# BNO005.net
KiCad netlist of a schematic drawn in Altium Designer
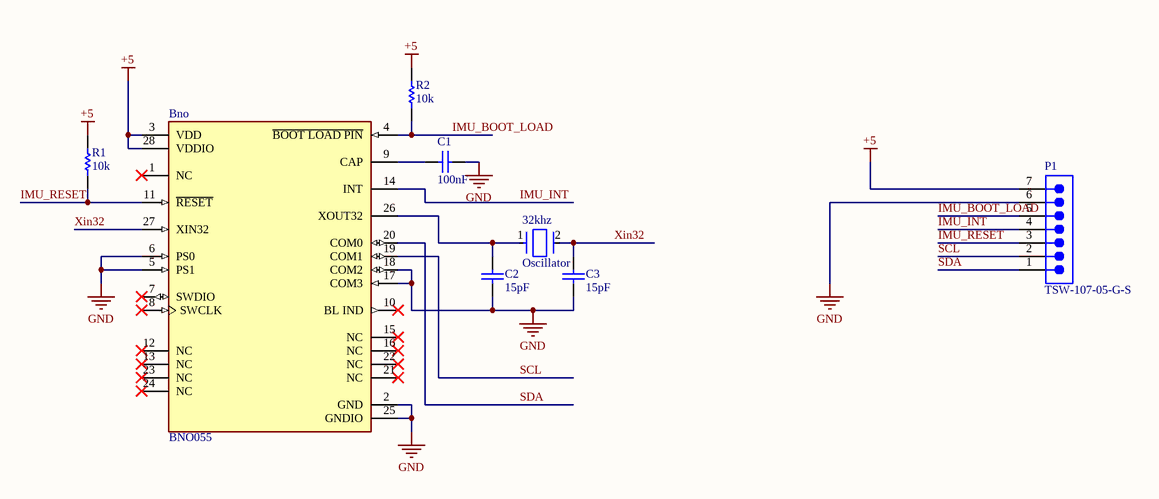
[diagram p0: BNO005.SchDoc]

(export (version "E")
  (design (tool "Eeschema 10.0.6"))
  (components
    (comp (ref "32khz")
      (value "Oscillator")
      (footprint "FP-NX2012SA-MFG")
      (description "CRYSTAL 32.7680KHZ 12.5PF SMD")
      (libsource (lib "Altium Content Vault") (part "c23a69dc6c9e2f18f2079038eb95dd1"))
    )
    (comp (ref "Bno")
      (value "BNO055")
      (footprint "FP-BNO055-MFG")
      (description "IMU ACCEL/GYRO/MAG I2C 28LGA")
      (libsource (lib "Altium Content Vault") (part "ba837af00a0b6167256f888b31462b1"))
    )
    (comp (ref "C1")
      (value "100nF")
      (footprint "CAPC1608X90X35ML10T15")
      (description "Chip Capacitor, 0.1 uF, +/- 10%, 50 V, -55 to 125 degC, 0603 (1608 Metric), RoHS, Tape and Reel")
      (fields (field (name "TOLERANCE") "10%") (field (name "VOLTAGE") "50V"))
      (libsource (lib "Altium Content Vault") (part "CAP-NP-2"))
    )
    (comp (ref "C2")
      (value "15pF")
      (footprint "CAPC1608X90X35ML10T15")
      (fields (field (name "PART NUMBER") "GRM1885C1H150JA01D") (field (name "MANUFACTURER") "Murata"))
      (libsource (lib "Altium Content Vault") (part "CAP"))
    )
    (comp (ref "C3")
      (value "15pF")
      (footprint "CAPC1608X90X35ML10T15")
      (fields (field (name "PART NUMBER") "GRM1885C1H150JA01D") (field (name "MANUFACTURER") "Murata"))
      (libsource (lib "Altium Content Vault") (part "CAP"))
    )
    (comp (ref "P1")
      (value "TSW-107-05-G-S")
      (footprint "SMTC-TSW-107-05-X-S")
      (description "0.025\" SQ Post Header, Through-hole, Vertical, -55 to 125 degC, 2.54 mm Pitch, 7-Pin, Male, RoHS")
      (fields (field (name "MANUFACTURER") "Samtec"))
      (libsource (lib "Altium Content Vault") (part "SMTC-TSW-107-05-X-S"))
    )
    (comp (ref "R1")
      (value "10k")
      (footprint "RESC1609X55X30LL15T15")
      (description "Chip Resistor, 10 KOhm, +/- 1%, 0.1 W, -55 to 155 degC, 0603 (1608 Metric), RoHS, Tape and Reel")
      (fields (field (name "TOLERANCE") "1%") (field (name "MANUFACTURER") "Panasonic"))
      (libsource (lib "Altium Content Vault") (part "RES-2"))
    )
    (comp (ref "R2")
      (value "10k")
      (footprint "RESC1609X55X30LL15T15")
      (description "Chip Resistor, 10 KOhm, +/- 1%, 0.1 W, -55 to 155 degC, 0603 (1608 Metric), RoHS, Tape and Reel")
      (fields (field (name "TOLERANCE") "1%") (field (name "MANUFACTURER") "Panasonic"))
      (libsource (lib "Altium Content Vault") (part "RES-2"))
    )
  )
  (nets
    (net (code "1") (name "+5") (class "Default")
      (node (ref "Bno") (pin "28") (pinfunction "VDDIO_28") (pintype "power_in"))
      (node (ref "Bno") (pin "3") (pinfunction "VDD_3") (pintype "power_in"))
      (node (ref "P1") (pin "7") (pinfunction "7_7") (pintype "passive"))
      (node (ref "R1") (pin "2") (pinfunction "2_2") (pintype "passive"))
      (node (ref "R2") (pin "2") (pinfunction "2_2") (pintype "passive"))
    )
    (net (code "2") (name "/IMU_BOOT_LOAD") (class "Default")
      (node (ref "Bno") (pin "4") (pinfunction "~{BOOT_LOAD_PIN}_4") (pintype "input"))
      (node (ref "P1") (pin "5") (pinfunction "5_5") (pintype "passive"))
      (node (ref "R2") (pin "1") (pinfunction "1_1") (pintype "passive"))
    )
    (net (code "3") (name "/IMU_INT") (class "Default")
      (node (ref "Bno") (pin "14") (pinfunction "INT_14") (pintype "passive"))
      (node (ref "P1") (pin "4") (pinfunction "4_4") (pintype "passive"))
    )
    (net (code "4") (name "/IMU_RESET") (class "Default")
      (node (ref "Bno") (pin "11") (pinfunction "~{RESET}_11") (pintype "input"))
      (node (ref "P1") (pin "3") (pinfunction "3_3") (pintype "passive"))
      (node (ref "R1") (pin "1") (pinfunction "1_1") (pintype "passive"))
    )
    (net (code "5") (name "/SCL") (class "Default")
      (node (ref "Bno") (pin "19") (pinfunction "COM1_19") (pintype "bidirectional"))
      (node (ref "P1") (pin "2") (pinfunction "2_2") (pintype "passive"))
    )
    (net (code "6") (name "/SDA") (class "Default")
      (node (ref "Bno") (pin "20") (pinfunction "COM0_20") (pintype "bidirectional"))
      (node (ref "P1") (pin "1") (pinfunction "1_1") (pintype "passive"))
    )
    (net (code "7") (name "/Xin32") (class "Default")
      (node (ref "32khz") (pin "2") (pinfunction "2_2") (pintype "passive"))
      (node (ref "Bno") (pin "27") (pinfunction "XIN32_27") (pintype "input"))
      (node (ref "C3") (pin "2") (pinfunction "2_2") (pintype "passive"))
    )
    (net (code "8") (name "GND") (class "Default")
      (node (ref "Bno") (pin "17") (pinfunction "COM3_17") (pintype "input"))
      (node (ref "Bno") (pin "18") (pinfunction "COM2_18") (pintype "bidirectional"))
      (node (ref "Bno") (pin "2") (pinfunction "GND_2") (pintype "power_in"))
      (node (ref "Bno") (pin "25") (pinfunction "GNDIO_25") (pintype "power_in"))
      (node (ref "Bno") (pin "5") (pinfunction "PS1_5") (pintype "input"))
      (node (ref "Bno") (pin "6") (pinfunction "PS0_6") (pintype "input"))
      (node (ref "C1") (pin "2") (pinfunction "2_2") (pintype "passive"))
      (node (ref "C2") (pin "1") (pinfunction "1_1") (pintype "passive"))
      (node (ref "C3") (pin "1") (pinfunction "1_1") (pintype "passive"))
      (node (ref "P1") (pin "6") (pinfunction "6_6") (pintype "passive"))
    )
    (net (code "9") (name "Net-(Bno-CAP)") (class "Default")
      (node (ref "Bno") (pin "9") (pinfunction "CAP_9") (pintype "passive"))
      (node (ref "C1") (pin "1") (pinfunction "1_1") (pintype "passive"))
    )
    (net (code "10") (name "Net-(Bno-XOUT32)") (class "Default")
      (node (ref "32khz") (pin "1") (pinfunction "1_1") (pintype "passive"))
      (node (ref "Bno") (pin "26") (pinfunction "XOUT32_26") (pintype "passive"))
      (node (ref "C2") (pin "2") (pinfunction "2_2") (pintype "passive"))
    )
    (net (code "11") (name "unconnected-(Bno-BL_IND-Pad10)") (class "Default")
      (node (ref "Bno") (pin "10") (pinfunction "BL_IND_10") (pintype "output+no_connect"))
    )
    (net (code "12") (name "unconnected-(Bno-NC-Pad1)") (class "Default")
      (node (ref "Bno") (pin "1") (pinfunction "NC_1") (pintype "passive+no_connect"))
    )
    (net (code "13") (name "unconnected-(Bno-NC-Pad12)") (class "Default")
      (node (ref "Bno") (pin "12") (pinfunction "NC_12") (pintype "passive+no_connect"))
    )
    (net (code "14") (name "unconnected-(Bno-NC-Pad13)") (class "Default")
      (node (ref "Bno") (pin "13") (pinfunction "NC_13") (pintype "passive+no_connect"))
    )
    (net (code "15") (name "unconnected-(Bno-NC-Pad15)") (class "Default")
      (node (ref "Bno") (pin "15") (pinfunction "NC_15") (pintype "passive+no_connect"))
    )
    (net (code "16") (name "unconnected-(Bno-NC-Pad16)") (class "Default")
      (node (ref "Bno") (pin "16") (pinfunction "NC_16") (pintype "passive+no_connect"))
    )
    (net (code "17") (name "unconnected-(Bno-NC-Pad21)") (class "Default")
      (node (ref "Bno") (pin "21") (pinfunction "NC_21") (pintype "passive+no_connect"))
    )
    (net (code "18") (name "unconnected-(Bno-NC-Pad22)") (class "Default")
      (node (ref "Bno") (pin "22") (pinfunction "NC_22") (pintype "passive+no_connect"))
    )
    (net (code "19") (name "unconnected-(Bno-NC-Pad23)") (class "Default")
      (node (ref "Bno") (pin "23") (pinfunction "NC_23") (pintype "passive+no_connect"))
    )
    (net (code "20") (name "unconnected-(Bno-NC-Pad24)") (class "Default")
      (node (ref "Bno") (pin "24") (pinfunction "NC_24") (pintype "passive+no_connect"))
    )
    (net (code "21") (name "unconnected-(Bno-SWCLK-Pad8)") (class "Default")
      (node (ref "Bno") (pin "8") (pinfunction "SWCLK_8") (pintype "input+no_connect"))
    )
    (net (code "22") (name "unconnected-(Bno-SWDIO-Pad7)") (class "Default")
      (node (ref "Bno") (pin "7") (pinfunction "SWDIO_7") (pintype "bidirectional+no_connect"))
    )
  )
)
